# Power_supplies.net
KiCad netlist of a schematic drawn in Altium Designer
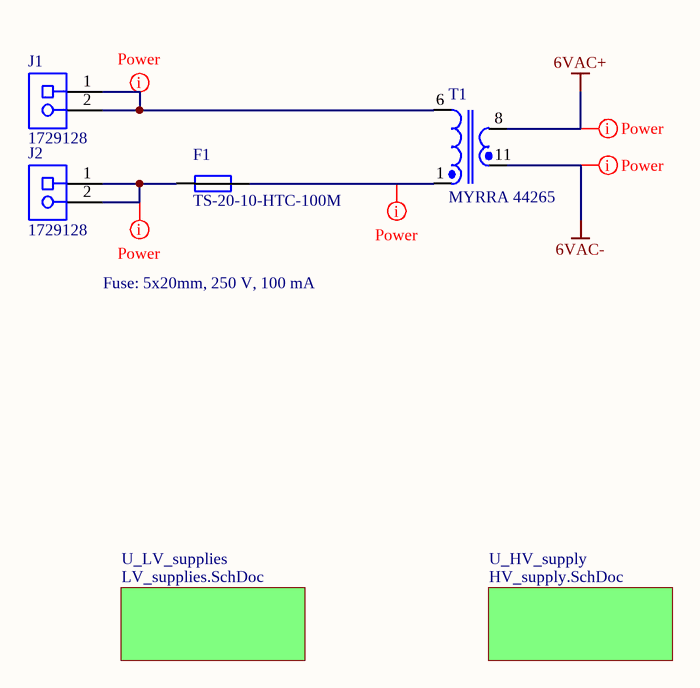
[diagram p0: Power_supplies.SchDoc]

(export (version "E")
  (design (tool "Eeschema 10.0.6"))
  (components
    (comp (ref "F1")
      (value "TS-20-10-HTC-100M")
      (footprint "TS-20-10-HTC-100M")
      (description "Fuse holder")
      (libsource (lib "Nixie") (part "TS-20-10-HTC-100M"))
    )
    (comp (ref "J1")
      (value "1729128")
      (footprint "1729128")
      (description "PCB Terminal Block, 13.5 A, 400 V, 2-Pin THD, RoHS, Bulk")
      (fields (field (name "MANUFACTURER") "Phoenix Contact"))
      (libsource (lib "Nixie") (part "1729128"))
    )
    (comp (ref "J2")
      (value "1729128")
      (footprint "1729128")
      (description "PCB Terminal Block, 13.5 A, 400 V, 2-Pin THD, RoHS, Bulk")
      (fields (field (name "MANUFACTURER") "Phoenix Contact"))
      (libsource (lib "Nixie") (part "1729128"))
    )
    (comp (ref "T1")
      (value "MYRRA 44265")
      (footprint "MYRRA_44265")
      (description "Isolation Transformer 10 VA, 230V, 6V")
      (libsource (lib "Nixie") (part "MYRRA 44265"))
    )
  )
  (nets
    (net (code "1") (name "6VAC+") (class "Default")
      (node (ref "T1") (pin "8") (pinfunction "8_8") (pintype "passive"))
    )
    (net (code "2") (name "6VAC-") (class "Default")
      (node (ref "T1") (pin "11") (pinfunction "11_11") (pintype "passive"))
    )
    (net (code "3") (name "Net-(F1-Pad1)") (class "Default")
      (node (ref "F1") (pin "1") (pinfunction "1_1") (pintype "passive"))
      (node (ref "J2") (pin "1") (pinfunction "1_1") (pintype "passive"))
      (node (ref "J2") (pin "2") (pinfunction "2_2") (pintype "passive"))
    )
    (net (code "4") (name "Net-(F1-Pad2)") (class "Default")
      (node (ref "F1") (pin "2") (pinfunction "2_2") (pintype "passive"))
      (node (ref "T1") (pin "1") (pinfunction "1_1") (pintype "passive"))
    )
    (net (code "5") (name "Net-(J1-Pad1)") (class "Default")
      (node (ref "J1") (pin "1") (pinfunction "1_1") (pintype "passive"))
      (node (ref "J1") (pin "2") (pinfunction "2_2") (pintype "passive"))
      (node (ref "T1") (pin "6") (pinfunction "6_6") (pintype "passive"))
    )
  )
)
